# CapSense.net
KiCad netlist of a schematic drawn in Altium Designer
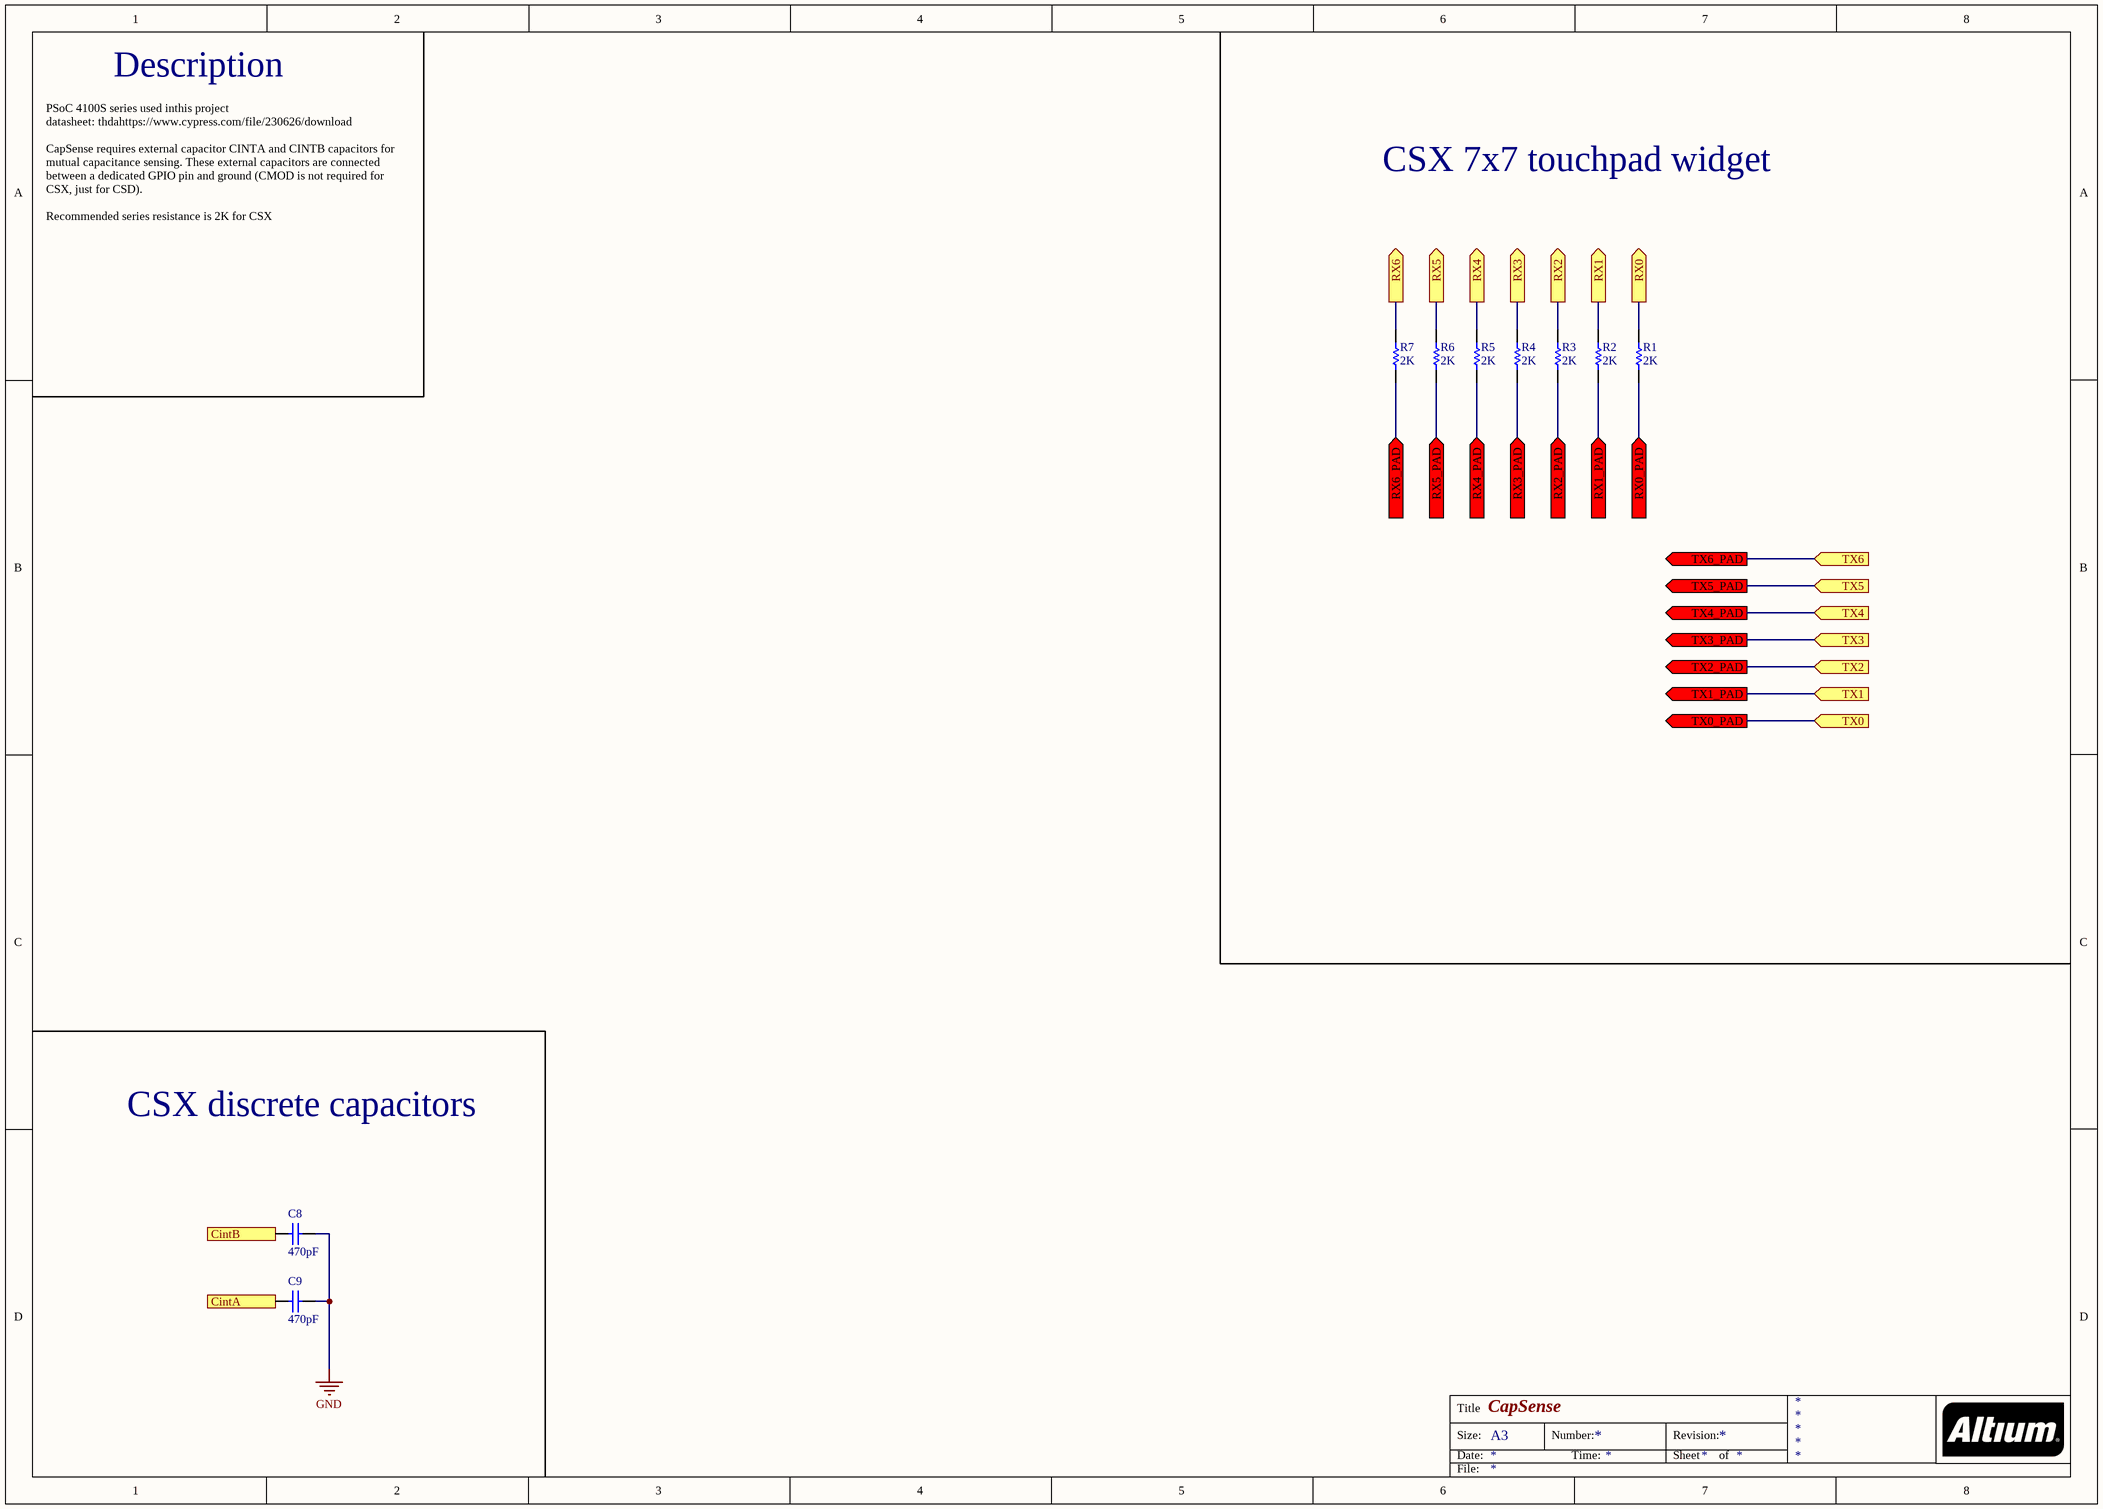
[diagram p0: CapSense.SchDoc]

(export (version "E")
  (design (tool "Eeschema 10.0.6"))
  (components
    (comp (ref "C8")
      (value "470pF")
      (footprint "CAPC0603(1608)100_N")
      (description "CAP 470pF 10V ±10% 0603 (1608 Metric) Thickness 1mm SMD")
      (fields (field (name "TOLERANCE") "Â±10%"))
      (libsource (lib "Altium Content Vault") (part "CAP"))
    )
    (comp (ref "C9")
      (value "470pF")
      (footprint "CAPC0603(1608)100_N")
      (description "CAP 470pF 10V ±10% 0603 (1608 Metric) Thickness 1mm SMD")
      (fields (field (name "TOLERANCE") "Â±10%"))
      (libsource (lib "Altium Content Vault") (part "CAP"))
    )
    (comp (ref "R1")
      (value "2K")
      (footprint "RESC0603(1608)_N")
      (description "2K 0.1W 5% 0603 (1608 Metric)  SMD")
      (fields (field (name "TOLERANCE") "5 %") (field (name "POWER") "0.1 W"))
      (libsource (lib "Altium Content Vault") (part "RES"))
    )
    (comp (ref "R2")
      (value "2K")
      (footprint "RESC0603(1608)_N")
      (description "2K 0.1W 5% 0603 (1608 Metric)  SMD")
      (fields (field (name "TOLERANCE") "5 %") (field (name "POWER") "0.1 W"))
      (libsource (lib "Altium Content Vault") (part "RES"))
    )
    (comp (ref "R3")
      (value "2K")
      (footprint "RESC0603(1608)_N")
      (description "2K 0.1W 5% 0603 (1608 Metric)  SMD")
      (fields (field (name "TOLERANCE") "5 %") (field (name "POWER") "0.1 W"))
      (libsource (lib "Altium Content Vault") (part "RES"))
    )
    (comp (ref "R4")
      (value "2K")
      (footprint "RESC0603(1608)_N")
      (description "2K 0.1W 5% 0603 (1608 Metric)  SMD")
      (fields (field (name "TOLERANCE") "5 %") (field (name "POWER") "0.1 W"))
      (libsource (lib "Altium Content Vault") (part "RES"))
    )
    (comp (ref "R5")
      (value "2K")
      (footprint "RESC0603(1608)_N")
      (description "2K 0.1W 5% 0603 (1608 Metric)  SMD")
      (fields (field (name "TOLERANCE") "5 %") (field (name "POWER") "0.1 W"))
      (libsource (lib "Altium Content Vault") (part "RES"))
    )
    (comp (ref "R6")
      (value "2K")
      (footprint "RESC0603(1608)_N")
      (description "2K 0.1W 5% 0603 (1608 Metric)  SMD")
      (fields (field (name "TOLERANCE") "5 %") (field (name "POWER") "0.1 W"))
      (libsource (lib "Altium Content Vault") (part "RES"))
    )
    (comp (ref "R7")
      (value "2K")
      (footprint "RESC0603(1608)_N")
      (description "2K 0.1W 5% 0603 (1608 Metric)  SMD")
      (fields (field (name "TOLERANCE") "5 %") (field (name "POWER") "0.1 W"))
      (libsource (lib "Altium Content Vault") (part "RES"))
    )
  )
  (nets
    (net (code "1") (name "/CintA") (class "Default")
      (node (ref "C9") (pin "1") (pinfunction "1_1") (pintype "passive"))
    )
    (net (code "2") (name "/CintB") (class "Default")
      (node (ref "C8") (pin "1") (pinfunction "1_1") (pintype "passive"))
    )
    (net (code "3") (name "/RX0") (class "Default")
      (node (ref "R1") (pin "1") (pinfunction "1_1") (pintype "passive"))
    )
    (net (code "4") (name "/RX0_PAD") (class "Default")
      (node (ref "R1") (pin "2") (pinfunction "2_2") (pintype "passive"))
    )
    (net (code "5") (name "/RX1") (class "Default")
      (node (ref "R2") (pin "1") (pinfunction "1_1") (pintype "passive"))
    )
    (net (code "6") (name "/RX1_PAD") (class "Default")
      (node (ref "R2") (pin "2") (pinfunction "2_2") (pintype "passive"))
    )
    (net (code "7") (name "/RX2") (class "Default")
      (node (ref "R3") (pin "1") (pinfunction "1_1") (pintype "passive"))
    )
    (net (code "8") (name "/RX2_PAD") (class "Default")
      (node (ref "R3") (pin "2") (pinfunction "2_2") (pintype "passive"))
    )
    (net (code "9") (name "/RX3") (class "Default")
      (node (ref "R4") (pin "1") (pinfunction "1_1") (pintype "passive"))
    )
    (net (code "10") (name "/RX3_PAD") (class "Default")
      (node (ref "R4") (pin "2") (pinfunction "2_2") (pintype "passive"))
    )
    (net (code "11") (name "/RX4") (class "Default")
      (node (ref "R5") (pin "1") (pinfunction "1_1") (pintype "passive"))
    )
    (net (code "12") (name "/RX4_PAD") (class "Default")
      (node (ref "R5") (pin "2") (pinfunction "2_2") (pintype "passive"))
    )
    (net (code "13") (name "/RX5") (class "Default")
      (node (ref "R6") (pin "1") (pinfunction "1_1") (pintype "passive"))
    )
    (net (code "14") (name "/RX5_PAD") (class "Default")
      (node (ref "R6") (pin "2") (pinfunction "2_2") (pintype "passive"))
    )
    (net (code "15") (name "/RX6") (class "Default")
      (node (ref "R7") (pin "1") (pinfunction "1_1") (pintype "passive"))
    )
    (net (code "16") (name "/RX6_PAD") (class "Default")
      (node (ref "R7") (pin "2") (pinfunction "2_2") (pintype "passive"))
    )
    (net (code "24") (name "GND") (class "Default")
      (node (ref "C8") (pin "2") (pinfunction "2_2") (pintype "passive"))
      (node (ref "C9") (pin "2") (pinfunction "2_2") (pintype "passive"))
    )
  )
)
